# TI_DS26C32AT.net
KiCad netlist of a schematic drawn in Altium Designer
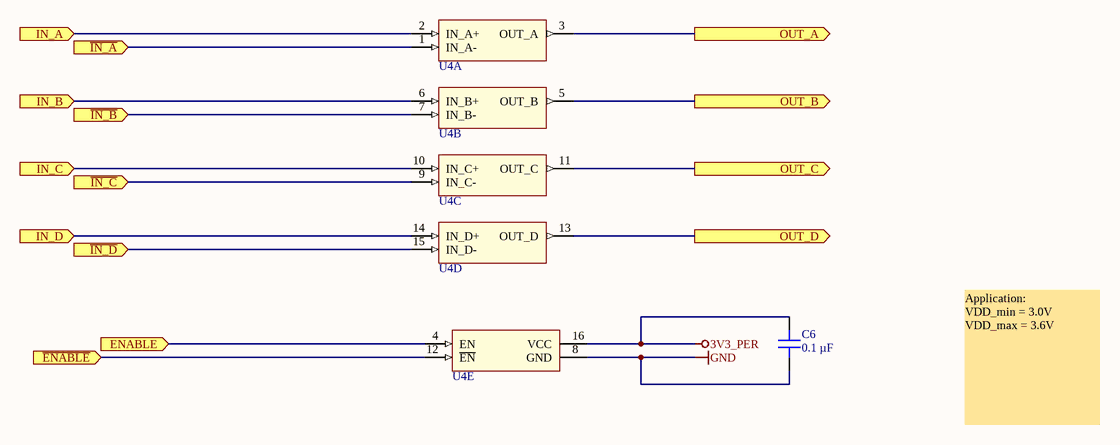
[diagram p0: TI_DS26C32AT.SchDoc]

(export (version "E")
  (design (tool "Eeschema 10.0.6"))
  (components
    (comp (ref "C6")
      (value "0.1 µF")
      (footprint "C_0603")
      (description "Capacitor 0603, 50 VDC, 0.1 µF, X7R")
      (fields
        (field (name "MANUFACTURER PART NUMBER") "C0603X104K5RAC7411")
        (field (name "MANUFACTURER") "KEMET")
        (field (name "CREATED FROM") "MGremer")
      )
      (libsource (lib "user") (part "Capacitor"))
    )
    (comp (ref "U4")
      (value "DS26LV32ATM/NOPB")
      (footprint "TI_D-R-PDSO-G16_N")
      (description "3V Enhanced CMOS Quad Differential Line Receiver, 16-pin Narrow SOIC, Pb-Free")
      (fields
        (field (name "MANUFACTURER") "Texas Instruments")
        (field (name "LCSC PART NUMBER") "C59861")
        (field (name "CREATED FROM") "T. Wendt")
      )
      (libsource (lib "user") (part "DS26LV32ATM"))
    )
  )
  (nets
    (net (code "1") (name "/ENABLE") (class "Default")
      (node (ref "U4") (pin "4") (pinfunction "EN_4") (pintype "input"))
    )
    (net (code "2") (name "/IN_A") (class "Default")
      (node (ref "U4") (pin "2") (pinfunction "IN_A+_2") (pintype "input"))
    )
    (net (code "3") (name "/IN_B") (class "Default")
      (node (ref "U4") (pin "6") (pinfunction "IN_B+_6") (pintype "input"))
    )
    (net (code "4") (name "/IN_C") (class "Default")
      (node (ref "U4") (pin "10") (pinfunction "IN_C+_10") (pintype "input"))
    )
    (net (code "5") (name "/IN_D") (class "Default")
      (node (ref "U4") (pin "14") (pinfunction "IN_D+_14") (pintype "input"))
    )
    (net (code "6") (name "/OUT_A") (class "Default")
      (node (ref "U4") (pin "3") (pinfunction "OUT_A_3") (pintype "output"))
    )
    (net (code "7") (name "/OUT_B") (class "Default")
      (node (ref "U4") (pin "5") (pinfunction "OUT_B_5") (pintype "output"))
    )
    (net (code "8") (name "/OUT_C") (class "Default")
      (node (ref "U4") (pin "11") (pinfunction "OUT_C_11") (pintype "output"))
    )
    (net (code "9") (name "/OUT_D") (class "Default")
      (node (ref "U4") (pin "13") (pinfunction "OUT_D_13") (pintype "output"))
    )
    (net (code "10") (name "/~{ENABLE}") (class "Default")
      (node (ref "U4") (pin "12") (pinfunction "~{EN}_12") (pintype "input"))
    )
    (net (code "11") (name "/~{IN_A}") (class "Default")
      (node (ref "U4") (pin "1") (pinfunction "IN_A-_1") (pintype "input"))
    )
    (net (code "12") (name "/~{IN_B}") (class "Default")
      (node (ref "U4") (pin "7") (pinfunction "IN_B-_7") (pintype "input"))
    )
    (net (code "13") (name "/~{IN_C}") (class "Default")
      (node (ref "U4") (pin "9") (pinfunction "IN_C-_9") (pintype "input"))
    )
    (net (code "14") (name "/~{IN_D}") (class "Default")
      (node (ref "U4") (pin "15") (pinfunction "IN_D-_15") (pintype "input"))
    )
    (net (code "15") (name "3V3_PER") (class "Default")
      (node (ref "C6") (pin "2") (pinfunction "2_2") (pintype "passive"))
      (node (ref "U4") (pin "16") (pinfunction "VCC_16") (pintype "power_in"))
    )
    (net (code "16") (name "GND") (class "Default")
      (node (ref "C6") (pin "1") (pinfunction "1_1") (pintype "passive"))
      (node (ref "U4") (pin "8") (pinfunction "GND_8") (pintype "power_in"))
    )
  )
)
